# Design_Project.net
KiCad netlist of a schematic drawn in EAGLE
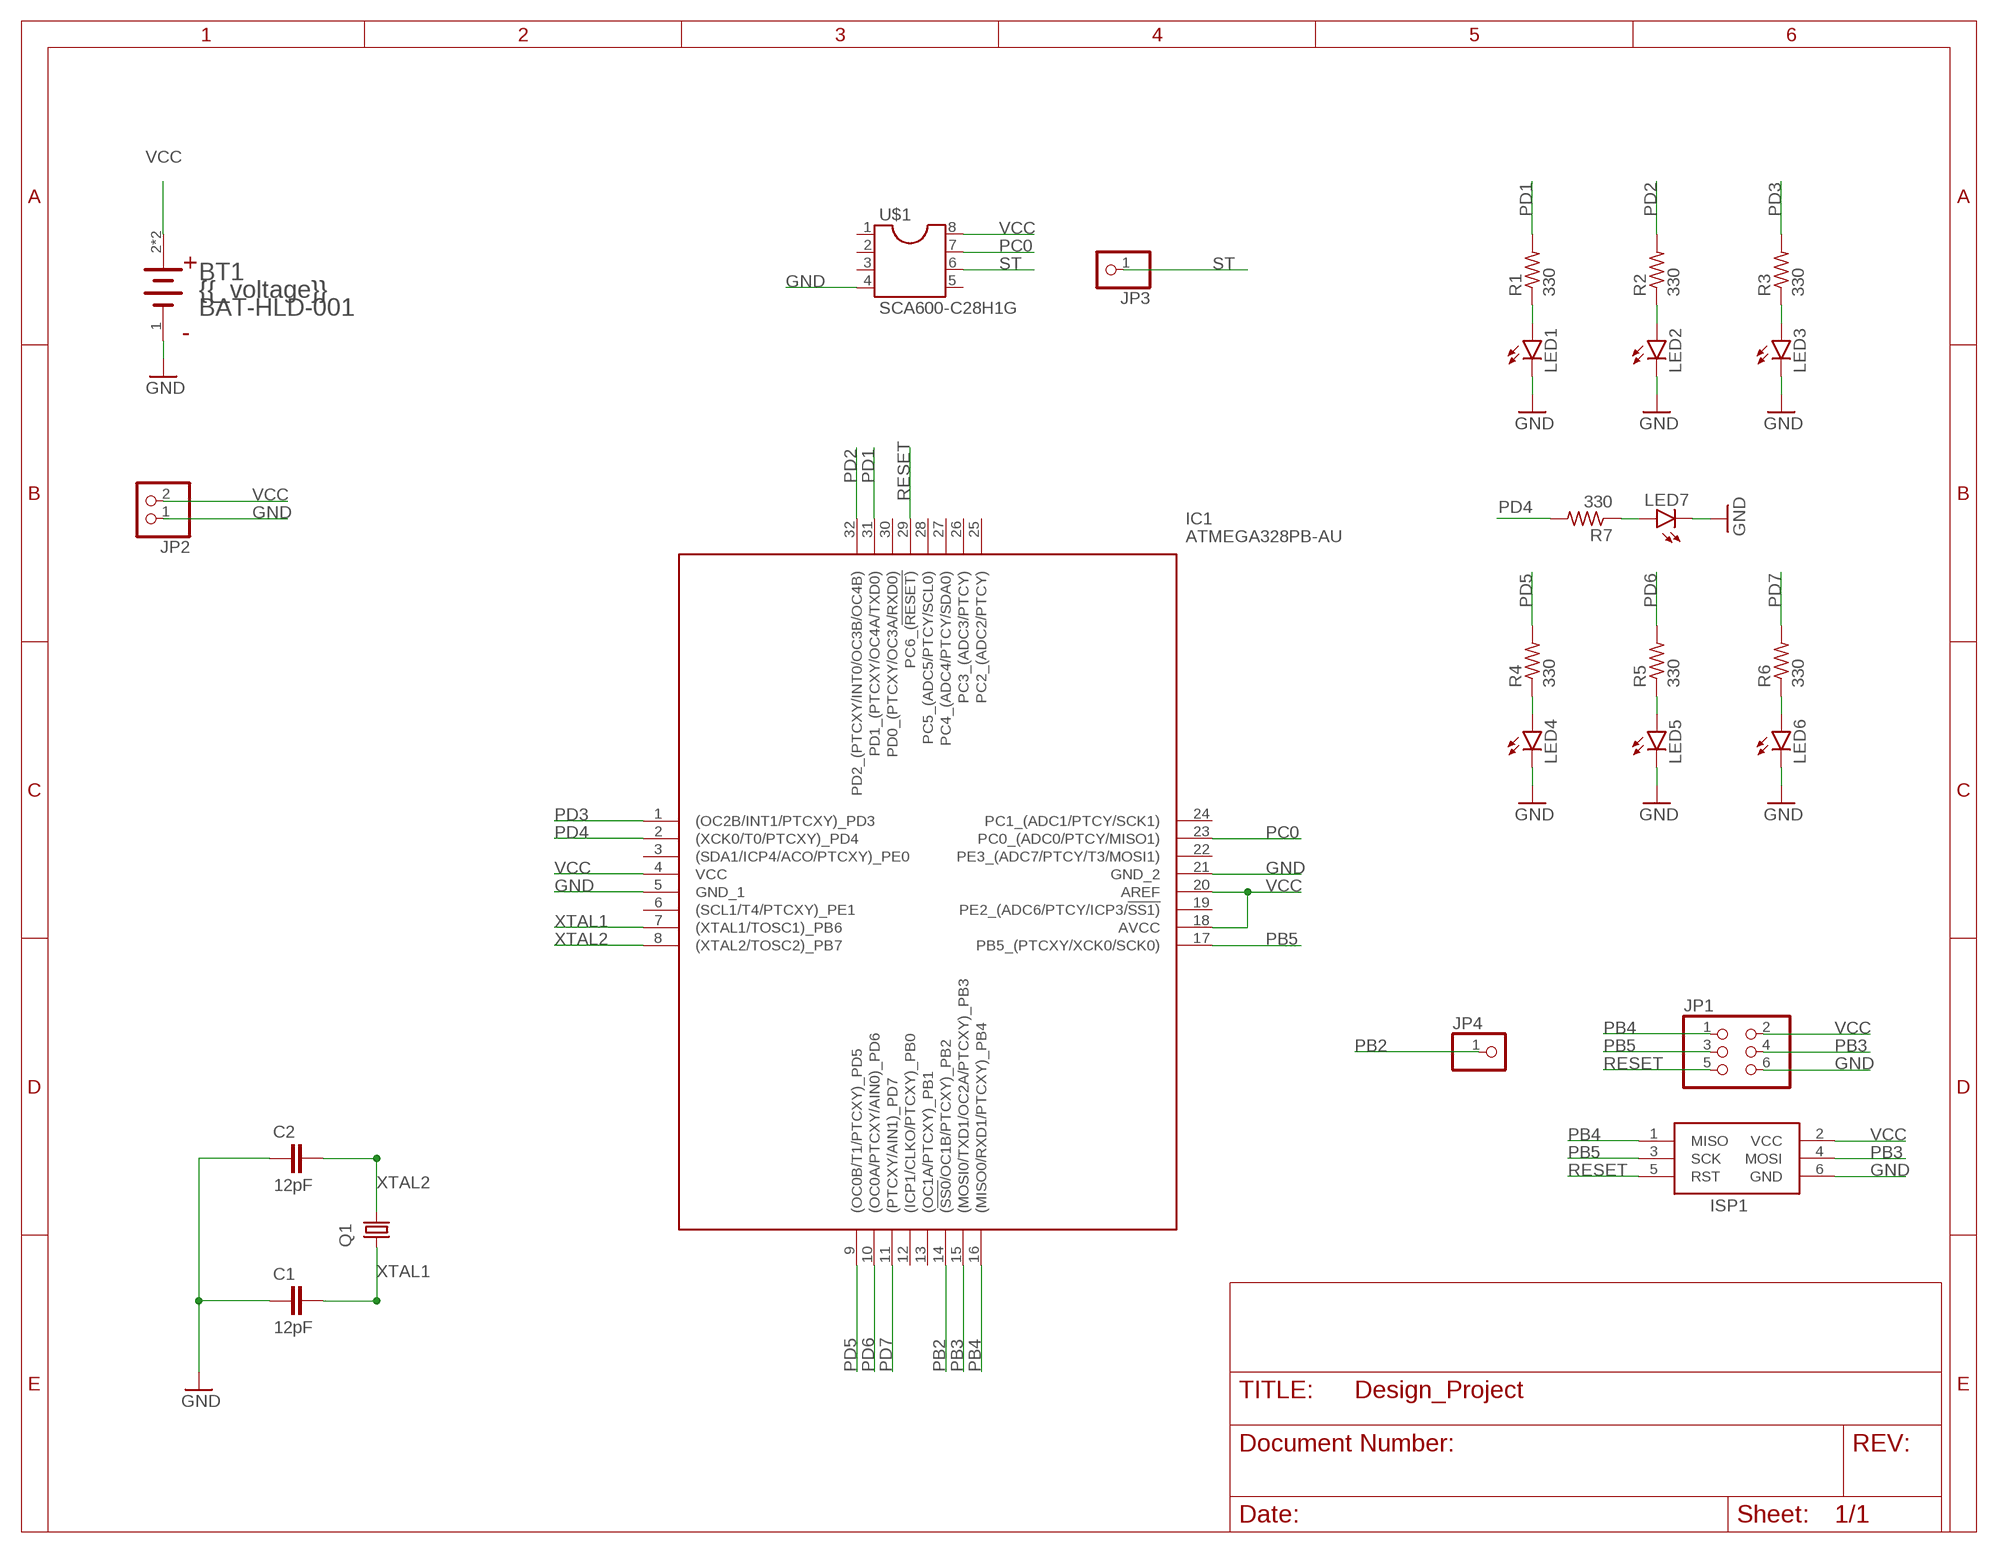
[diagram p0: schematic, sheet 1]

(export (version "E")
  (design (tool "Eeschema 10.0.6"))
  (components
    (comp (ref "BT1")
      (value "LINX_BAT-HLD-001LINX_BAT-HLD-001_0_0")
      (footprint "eagle-import:LINX_BAT-HLD-001_0")
      (fields
        (field (name "DIGIKEY_PART_NUMBER") "BAT-HLD-001-ND")
        (field (name "MF") "Linx")
        (field (name "MOUSER_PART_NUMBER") "712-BAT-HLD-001")
      )
      (libsource (lib "eagle-import") (part "LINX_BAT-HLD-001LINX_BAT-HLD-001_0_0"))
    )
    (comp (ref "C1")
      (value "12pF")
      (footprint "eagle-import:C0805")
      (libsource (lib "eagle-import") (part "C-EUC0805"))
    )
    (comp (ref "C2")
      (value "12pF")
      (footprint "eagle-import:C0805")
      (libsource (lib "eagle-import") (part "C-EUC0805"))
    )
    (comp (ref "IC1")
      (value "ATMEGA328PB-AU")
      (footprint "eagle-import:QFP80P900X900X120-32N")
      (fields (field (name "MOUSER_PART_NUMBER") "556-ATMEGA328PB-AU"))
      (libsource (lib "eagle-import") (part "ATMEGA328PB-AU"))
    )
    (comp (ref "ISP1")
      (value "AVRISP-6")
      (footprint "eagle-import:AVRISP")
      (libsource (lib "eagle-import") (part "AVRISP-6"))
    )
    (comp (ref "JP1")
      (value "PINHD-2X3")
      (footprint "eagle-import:2X03")
      (libsource (lib "eagle-import") (part "PINHD-2X3"))
    )
    (comp (ref "JP2")
      (value "PINHD-1X2")
      (footprint "eagle-import:1X02")
      (libsource (lib "eagle-import") (part "PINHD-1X2"))
    )
    (comp (ref "JP3")
      (value "PINHD-1X1")
      (footprint "eagle-import:1X01")
      (libsource (lib "eagle-import") (part "PINHD-1X1"))
    )
    (comp (ref "JP4")
      (value "PINHD-1X1")
      (footprint "eagle-import:1X01")
      (libsource (lib "eagle-import") (part "PINHD-1X1"))
    )
    (comp (ref "LED1")
      (value "LEDCHIPLED_0805")
      (footprint "eagle-import:CHIPLED_0805")
      (libsource (lib "eagle-import") (part "LEDCHIPLED_0805"))
    )
    (comp (ref "LED2")
      (value "LEDCHIPLED_0805")
      (footprint "eagle-import:CHIPLED_0805")
      (libsource (lib "eagle-import") (part "LEDCHIPLED_0805"))
    )
    (comp (ref "LED3")
      (value "LEDCHIPLED_0805")
      (footprint "eagle-import:CHIPLED_0805")
      (libsource (lib "eagle-import") (part "LEDCHIPLED_0805"))
    )
    (comp (ref "LED4")
      (value "LEDCHIPLED_0805")
      (footprint "eagle-import:CHIPLED_0805")
      (libsource (lib "eagle-import") (part "LEDCHIPLED_0805"))
    )
    (comp (ref "LED5")
      (value "LEDCHIPLED_0805")
      (footprint "eagle-import:CHIPLED_0805")
      (libsource (lib "eagle-import") (part "LEDCHIPLED_0805"))
    )
    (comp (ref "LED6")
      (value "LEDCHIPLED_0805")
      (footprint "eagle-import:CHIPLED_0805")
      (libsource (lib "eagle-import") (part "LEDCHIPLED_0805"))
    )
    (comp (ref "LED7")
      (value "LEDCHIPLED_0805")
      (footprint "eagle-import:CHIPLED_0805")
      (libsource (lib "eagle-import") (part "LEDCHIPLED_0805"))
    )
    (comp (ref "Q1")
      (value "CRYSTALHC49S")
      (footprint "eagle-import:HC49_S")
      (libsource (lib "eagle-import") (part "CRYSTALHC49S"))
    )
    (comp (ref "R1")
      (value "330")
      (footprint "eagle-import:M0805")
      (libsource (lib "eagle-import") (part "R-US_M0805"))
    )
    (comp (ref "R2")
      (value "330")
      (footprint "eagle-import:M0805")
      (libsource (lib "eagle-import") (part "R-US_M0805"))
    )
    (comp (ref "R3")
      (value "330")
      (footprint "eagle-import:M0805")
      (libsource (lib "eagle-import") (part "R-US_M0805"))
    )
    (comp (ref "R4")
      (value "330")
      (footprint "eagle-import:M0805")
      (libsource (lib "eagle-import") (part "R-US_M0805"))
    )
    (comp (ref "R5")
      (value "330")
      (footprint "eagle-import:M0805")
      (libsource (lib "eagle-import") (part "R-US_M0805"))
    )
    (comp (ref "R6")
      (value "330")
      (footprint "eagle-import:M0805")
      (libsource (lib "eagle-import") (part "R-US_M0805"))
    )
    (comp (ref "R7")
      (value "330")
      (footprint "eagle-import:M0805")
      (libsource (lib "eagle-import") (part "R-US_M0805"))
    )
    (comp (ref "U$1")
      (value "SCA600-C28H1G")
      (footprint "eagle-import:SCA600-C28H1G")
      (libsource (lib "eagle-import") (part "SCA600-C28H1G"))
    )
  )
  (nets
    (net (code "1") (name "/PB2") (class "Default")
      (node (ref "IC1") (pin "14") (pinfunction "(~{SS0}/OC1B/PTCXY)_PB2_14") (pintype "bidirectional"))
      (node (ref "JP4") (pin "1") (pinfunction "1_1") (pintype "passive"))
    )
    (net (code "2") (name "/PB3") (class "Default")
      (node (ref "IC1") (pin "15") (pinfunction "(MOSI0/TXD1/OC2A/PTCXY)_PB3_15") (pintype "bidirectional"))
      (node (ref "ISP1") (pin "4") (pinfunction "MOSI_4") (pintype "output"))
      (node (ref "JP1") (pin "4") (pinfunction "4_4") (pintype "passive"))
    )
    (net (code "3") (name "/PB4") (class "Default")
      (node (ref "IC1") (pin "16") (pinfunction "(MISO0/RXD1/PTCXY)_PB4_16") (pintype "bidirectional"))
      (node (ref "ISP1") (pin "1") (pinfunction "MISO_1") (pintype "input"))
      (node (ref "JP1") (pin "1") (pinfunction "1_1") (pintype "passive"))
    )
    (net (code "4") (name "/PB5") (class "Default")
      (node (ref "IC1") (pin "17") (pinfunction "PB5_(PTCXY/XCK0/SCK0)_17") (pintype "bidirectional"))
      (node (ref "ISP1") (pin "3") (pinfunction "SCK_3") (pintype "output"))
      (node (ref "JP1") (pin "3") (pinfunction "3_3") (pintype "passive"))
    )
    (net (code "5") (name "/PC0") (class "Default")
      (node (ref "IC1") (pin "23") (pinfunction "PC0_(ADC0/PTCY/MISO1)_23") (pintype "bidirectional"))
      (node (ref "U$1") (pin "7") (pinfunction "7_7") (pintype "passive"))
    )
    (net (code "6") (name "/PD1") (class "Default")
      (node (ref "IC1") (pin "31") (pinfunction "PD1_(PTCXY/OC4A/TXD0)_31") (pintype "bidirectional"))
      (node (ref "R1") (pin "2") (pinfunction "2_2") (pintype "passive"))
    )
    (net (code "7") (name "/PD2") (class "Default")
      (node (ref "IC1") (pin "32") (pinfunction "PD2_(PTCXY/INT0/OC3B/OC4B)_32") (pintype "bidirectional"))
      (node (ref "R2") (pin "2") (pinfunction "2_2") (pintype "passive"))
    )
    (net (code "8") (name "/PD3") (class "Default")
      (node (ref "IC1") (pin "1") (pinfunction "(OC2B/INT1/PTCXY)_PD3_1") (pintype "bidirectional"))
      (node (ref "R3") (pin "2") (pinfunction "2_2") (pintype "passive"))
    )
    (net (code "9") (name "/PD4") (class "Default")
      (node (ref "IC1") (pin "2") (pinfunction "(XCK0/T0/PTCXY)_PD4_2") (pintype "bidirectional"))
      (node (ref "R7") (pin "2") (pinfunction "2_2") (pintype "passive"))
    )
    (net (code "10") (name "/PD5") (class "Default")
      (node (ref "IC1") (pin "9") (pinfunction "(OC0B/T1/PTCXY)_PD5_9") (pintype "bidirectional"))
      (node (ref "R4") (pin "2") (pinfunction "2_2") (pintype "passive"))
    )
    (net (code "11") (name "/PD6") (class "Default")
      (node (ref "IC1") (pin "10") (pinfunction "(OC0A/PTCXY/AIN0)_PD6_10") (pintype "bidirectional"))
      (node (ref "R5") (pin "2") (pinfunction "2_2") (pintype "passive"))
    )
    (net (code "12") (name "/PD7") (class "Default")
      (node (ref "IC1") (pin "11") (pinfunction "(PTCXY/AIN1)_PD7_11") (pintype "bidirectional"))
      (node (ref "R6") (pin "2") (pinfunction "2_2") (pintype "passive"))
    )
    (net (code "13") (name "/RESET") (class "Default")
      (node (ref "IC1") (pin "29") (pinfunction "PC6_(~{RESET})_29") (pintype "bidirectional"))
      (node (ref "ISP1") (pin "5") (pinfunction "RST_5") (pintype "output"))
      (node (ref "JP1") (pin "5") (pinfunction "5_5") (pintype "passive"))
    )
    (net (code "14") (name "/ST") (class "Default")
      (node (ref "JP3") (pin "1") (pinfunction "1_1") (pintype "passive"))
      (node (ref "U$1") (pin "6") (pinfunction "6_6") (pintype "passive"))
    )
    (net (code "15") (name "/VCC") (class "Default")
      (node (ref "BT1") (pin "2") (pinfunction "ANODE_2") (pintype "bidirectional"))
      (node (ref "BT1") (pin "2-2") (pinfunction "ANODE_2-2") (pintype "bidirectional"))
      (node (ref "IC1") (pin "18") (pinfunction "AVCC_18") (pintype "bidirectional"))
      (node (ref "IC1") (pin "20") (pinfunction "AREF_20") (pintype "bidirectional"))
      (node (ref "IC1") (pin "4") (pinfunction "VCC_4") (pintype "bidirectional"))
      (node (ref "ISP1") (pin "2") (pinfunction "VCC_2") (pintype "power_in"))
      (node (ref "JP1") (pin "2") (pinfunction "2_2") (pintype "passive"))
      (node (ref "JP2") (pin "2") (pinfunction "2_2") (pintype "passive"))
      (node (ref "U$1") (pin "8") (pinfunction "8_8") (pintype "passive"))
    )
    (net (code "16") (name "/XTAL1") (class "Default")
      (node (ref "C1") (pin "2") (pinfunction "2_2") (pintype "passive"))
      (node (ref "IC1") (pin "7") (pinfunction "(XTAL1/TOSC1)_PB6_7") (pintype "bidirectional"))
      (node (ref "Q1") (pin "1") (pinfunction "1_1") (pintype "passive"))
    )
    (net (code "17") (name "/XTAL2") (class "Default")
      (node (ref "C2") (pin "2") (pinfunction "2_2") (pintype "passive"))
      (node (ref "IC1") (pin "8") (pinfunction "(XTAL2/TOSC2)_PB7_8") (pintype "bidirectional"))
      (node (ref "Q1") (pin "2") (pinfunction "2_2") (pintype "passive"))
    )
    (net (code "18") (name "GND") (class "Default")
      (node (ref "BT1") (pin "1") (pinfunction "CATHODE_1") (pintype "bidirectional"))
      (node (ref "C1") (pin "1") (pinfunction "1_1") (pintype "passive"))
      (node (ref "C2") (pin "1") (pinfunction "1_1") (pintype "passive"))
      (node (ref "IC1") (pin "21") (pinfunction "GND_2_21") (pintype "bidirectional"))
      (node (ref "IC1") (pin "5") (pinfunction "GND_1_5") (pintype "bidirectional"))
      (node (ref "ISP1") (pin "6") (pinfunction "GND_6") (pintype "power_in"))
      (node (ref "JP1") (pin "6") (pinfunction "6_6") (pintype "passive"))
      (node (ref "JP2") (pin "1") (pinfunction "1_1") (pintype "passive"))
      (node (ref "LED1") (pin "C") (pinfunction "C_C") (pintype "passive"))
      (node (ref "LED2") (pin "C") (pinfunction "C_C") (pintype "passive"))
      (node (ref "LED3") (pin "C") (pinfunction "C_C") (pintype "passive"))
      (node (ref "LED4") (pin "C") (pinfunction "C_C") (pintype "passive"))
      (node (ref "LED5") (pin "C") (pinfunction "C_C") (pintype "passive"))
      (node (ref "LED6") (pin "C") (pinfunction "C_C") (pintype "passive"))
      (node (ref "LED7") (pin "C") (pinfunction "C_C") (pintype "passive"))
      (node (ref "U$1") (pin "4") (pinfunction "4_4") (pintype "passive"))
    )
    (net (code "19") (name "Net-(LED1-PadA)") (class "Default")
      (node (ref "LED1") (pin "A") (pinfunction "A_A") (pintype "passive"))
      (node (ref "R1") (pin "1") (pinfunction "1_1") (pintype "passive"))
    )
    (net (code "20") (name "Net-(LED2-PadA)") (class "Default")
      (node (ref "LED2") (pin "A") (pinfunction "A_A") (pintype "passive"))
      (node (ref "R2") (pin "1") (pinfunction "1_1") (pintype "passive"))
    )
    (net (code "21") (name "Net-(LED3-PadA)") (class "Default")
      (node (ref "LED3") (pin "A") (pinfunction "A_A") (pintype "passive"))
      (node (ref "R3") (pin "1") (pinfunction "1_1") (pintype "passive"))
    )
    (net (code "22") (name "Net-(LED4-PadA)") (class "Default")
      (node (ref "LED4") (pin "A") (pinfunction "A_A") (pintype "passive"))
      (node (ref "R4") (pin "1") (pinfunction "1_1") (pintype "passive"))
    )
    (net (code "23") (name "Net-(LED5-PadA)") (class "Default")
      (node (ref "LED5") (pin "A") (pinfunction "A_A") (pintype "passive"))
      (node (ref "R5") (pin "1") (pinfunction "1_1") (pintype "passive"))
    )
    (net (code "24") (name "Net-(LED6-PadA)") (class "Default")
      (node (ref "LED6") (pin "A") (pinfunction "A_A") (pintype "passive"))
      (node (ref "R6") (pin "1") (pinfunction "1_1") (pintype "passive"))
    )
    (net (code "25") (name "Net-(LED7-PadA)") (class "Default")
      (node (ref "LED7") (pin "A") (pinfunction "A_A") (pintype "passive"))
      (node (ref "R7") (pin "1") (pinfunction "1_1") (pintype "passive"))
    )
    (net (code "26") (name "unconnected-(IC1-(ICP1{slash}CLKO{slash}PTCXY)_PB0-Pad12)") (class "Default")
      (node (ref "IC1") (pin "12") (pinfunction "(ICP1/CLKO/PTCXY)_PB0_12") (pintype "bidirectional"))
    )
    (net (code "27") (name "unconnected-(IC1-(OC1A{slash}PTCXY)_PB1-Pad13)") (class "Default")
      (node (ref "IC1") (pin "13") (pinfunction "(OC1A/PTCXY)_PB1_13") (pintype "bidirectional"))
    )
    (net (code "28") (name "unconnected-(IC1-(SCL1{slash}T4{slash}PTCXY)_PE1-Pad6)") (class "Default")
      (node (ref "IC1") (pin "6") (pinfunction "(SCL1/T4/PTCXY)_PE1_6") (pintype "bidirectional"))
    )
    (net (code "29") (name "unconnected-(IC1-(SDA1{slash}ICP4{slash}ACO{slash}PTCXY)_PE0-Pad3)") (class "Default")
      (node (ref "IC1") (pin "3") (pinfunction "(SDA1/ICP4/ACO/PTCXY)_PE0_3") (pintype "bidirectional"))
    )
    (net (code "30") (name "unconnected-(IC1-PC1_(ADC1{slash}PTCY{slash}SCK1)-Pad24)") (class "Default")
      (node (ref "IC1") (pin "24") (pinfunction "PC1_(ADC1/PTCY/SCK1)_24") (pintype "bidirectional"))
    )
    (net (code "31") (name "unconnected-(IC1-PC2_(ADC2{slash}PTCY)-Pad25)") (class "Default")
      (node (ref "IC1") (pin "25") (pinfunction "PC2_(ADC2/PTCY)_25") (pintype "bidirectional"))
    )
    (net (code "32") (name "unconnected-(IC1-PC3_(ADC3{slash}PTCY)-Pad26)") (class "Default")
      (node (ref "IC1") (pin "26") (pinfunction "PC3_(ADC3/PTCY)_26") (pintype "bidirectional"))
    )
    (net (code "33") (name "unconnected-(IC1-PC4_(ADC4{slash}PTCY{slash}SDA0)-Pad27)") (class "Default")
      (node (ref "IC1") (pin "27") (pinfunction "PC4_(ADC4/PTCY/SDA0)_27") (pintype "bidirectional"))
    )
    (net (code "34") (name "unconnected-(IC1-PC5_(ADC5{slash}PTCY{slash}SCL0)-Pad28)") (class "Default")
      (node (ref "IC1") (pin "28") (pinfunction "PC5_(ADC5/PTCY/SCL0)_28") (pintype "bidirectional"))
    )
    (net (code "35") (name "unconnected-(IC1-PD0_(PTCXY{slash}OC3A{slash}RXD0)-Pad30)") (class "Default")
      (node (ref "IC1") (pin "30") (pinfunction "PD0_(PTCXY/OC3A/RXD0)_30") (pintype "bidirectional"))
    )
    (net (code "36") (name "unconnected-(IC1-PE2_(ADC6{slash}PTCY{slash}ICP3{slash}~{SS1})-Pad19)") (class "Default")
      (node (ref "IC1") (pin "19") (pinfunction "PE2_(ADC6/PTCY/ICP3/~{SS1})_19") (pintype "bidirectional"))
    )
    (net (code "37") (name "unconnected-(IC1-PE3_(ADC7{slash}PTCY{slash}T3{slash}MOSI1)-Pad22)") (class "Default")
      (node (ref "IC1") (pin "22") (pinfunction "PE3_(ADC7/PTCY/T3/MOSI1)_22") (pintype "bidirectional"))
    )
    (net (code "38") (name "unconnected-(U$1-Pad1)") (class "Default")
      (node (ref "U$1") (pin "1") (pinfunction "1_1") (pintype "passive"))
    )
    (net (code "39") (name "unconnected-(U$1-Pad2)") (class "Default")
      (node (ref "U$1") (pin "2") (pinfunction "2_2") (pintype "passive"))
    )
    (net (code "40") (name "unconnected-(U$1-Pad3)") (class "Default")
      (node (ref "U$1") (pin "3") (pinfunction "3_3") (pintype "passive"))
    )
    (net (code "41") (name "unconnected-(U$1-Pad5)") (class "Default")
      (node (ref "U$1") (pin "5") (pinfunction "5_5") (pintype "passive"))
    )
  )
)
